# Own_USB-C_Breakout_v3_1_Final.net
KiCad netlist of a schematic drawn in EAGLE
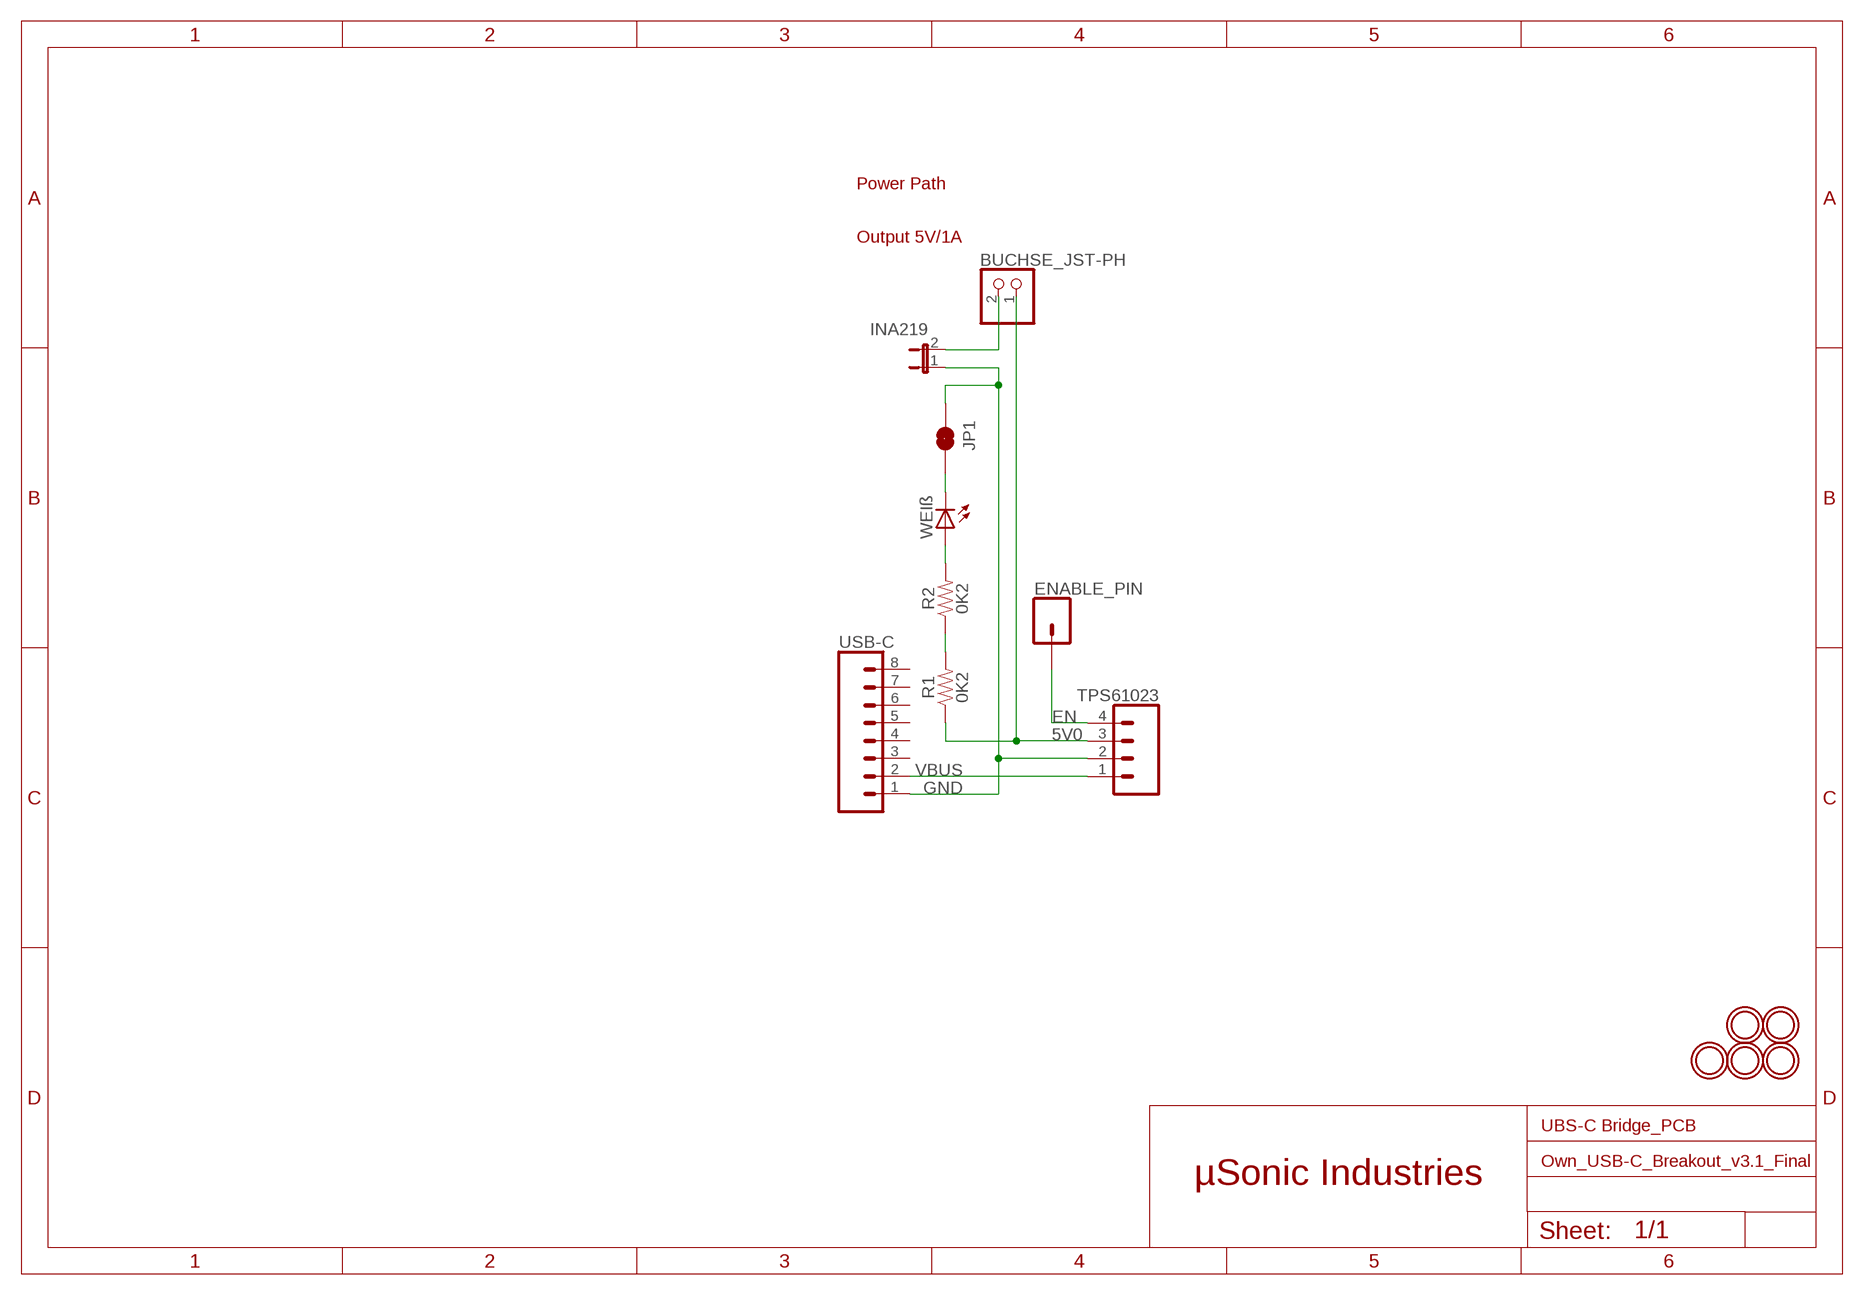
[diagram p0: schematic, sheet 1]

(export (version "E")
  (design (tool "Eeschema 10.0.6"))
  (components
    (comp (ref "BUCHSE_JST-PH")
      (value "JST_2PINOWN")
      (footprint "eagle-import:JST-PH-2-THMOWN")
      (libsource (lib "eagle-import") (part "JST_2PINOWN"))
    )
    (comp (ref "ENABLE_PIN")
      (value "CONN_01PTH_NO_SILK_YES_STOP")
      (footprint "eagle-import:1X01_NO_SILK")
      (libsource (lib "eagle-import") (part "CONN_01PTH_NO_SILK_YES_STOP"))
    )
    (comp (ref "INA219")
      (value "JP1E")
      (footprint "eagle-import:JP1")
      (libsource (lib "eagle-import") (part "JP1E"))
    )
    (comp (ref "JP1")
      (value "JUMPER-SMT_2_NC_TRACE_SILK")
      (footprint "eagle-import:SMT-JUMPER_2_NC_TRACE_SILK")
      (libsource (lib "eagle-import") (part "JUMPER-SMT_2_NC_TRACE_SILK"))
    )
    (comp (ref "R1")
      (value "0K2")
      (footprint "eagle-import:0805")
      (libsource (lib "eagle-import") (part "RESISTOR0805"))
    )
    (comp (ref "R2")
      (value "0K2")
      (footprint "eagle-import:0805")
      (libsource (lib "eagle-import") (part "RESISTOR0805"))
    )
    (comp (ref "TPS61023")
      (value "CONN_041X04_NO_SILK")
      (footprint "eagle-import:1X04_NO_SILK")
      (libsource (lib "eagle-import") (part "CONN_041X04_NO_SILK"))
    )
    (comp (ref "U$1")
      (value "MOUNTINGHOLE2.5")
      (footprint "eagle-import:MOUNTINGHOLE_2.5_PLATED")
      (libsource (lib "eagle-import") (part "MOUNTINGHOLE2.5"))
    )
    (comp (ref "U$2")
      (value "MOUNTINGHOLE2.5")
      (footprint "eagle-import:MOUNTINGHOLE_2.5_PLATED")
      (libsource (lib "eagle-import") (part "MOUNTINGHOLE2.5"))
    )
    (comp (ref "U$10")
      (value "MOUNTINGHOLE2.5")
      (footprint "eagle-import:MOUNTINGHOLE_2.5_PLATED")
      (libsource (lib "eagle-import") (part "MOUNTINGHOLE2.5"))
    )
    (comp (ref "U$11")
      (value "MOUNTINGHOLE2.5")
      (footprint "eagle-import:MOUNTINGHOLE_2.5_PLATED")
      (libsource (lib "eagle-import") (part "MOUNTINGHOLE2.5"))
    )
    (comp (ref "U$14")
      (value "MOUNTINGHOLE2.5")
      (footprint "eagle-import:MOUNTINGHOLE_2.5_PLATED")
      (libsource (lib "eagle-import") (part "MOUNTINGHOLE2.5"))
    )
    (comp (ref "USB-C")
      (value "CONN_08NO_SILK_FEMALE_PTH")
      (footprint "eagle-import:1X08_NO_SILK")
      (libsource (lib "eagle-import") (part "CONN_08NO_SILK_FEMALE_PTH"))
    )
    (comp (ref "WEIß")
      (value "LEDCHIPLED_0805")
      (footprint "eagle-import:CHIPLED_0805")
      (libsource (lib "eagle-import") (part "LEDCHIPLED_0805"))
    )
  )
  (nets
    (net (code "1") (name "/5V0") (class "Default")
      (node (ref "BUCHSE_JST-PH") (pin "1") (pinfunction "2_1") (pintype "passive"))
      (node (ref "R1") (pin "1") (pinfunction "1_1") (pintype "passive"))
      (node (ref "TPS61023") (pin "3") (pinfunction "3_3") (pintype "passive"))
    )
    (net (code "2") (name "/EN") (class "Default")
      (node (ref "ENABLE_PIN") (pin "1") (pinfunction "1_1") (pintype "passive"))
      (node (ref "TPS61023") (pin "4") (pinfunction "4_4") (pintype "passive"))
    )
    (net (code "3") (name "/GND") (class "Default")
      (node (ref "INA219") (pin "1") (pinfunction "1_1") (pintype "passive"))
      (node (ref "JP1") (pin "1") (pinfunction "1_1") (pintype "passive"))
      (node (ref "TPS61023") (pin "2") (pinfunction "2_2") (pintype "passive"))
      (node (ref "USB-C") (pin "1") (pinfunction "1_1") (pintype "passive"))
    )
    (net (code "4") (name "/VBUS") (class "Default")
      (node (ref "TPS61023") (pin "1") (pinfunction "1_1") (pintype "passive"))
      (node (ref "USB-C") (pin "2") (pinfunction "2_2") (pintype "passive"))
    )
    (net (code "5") (name "Net-(BUCHSE_JST-PH-1)") (class "Default")
      (node (ref "BUCHSE_JST-PH") (pin "2") (pinfunction "1_2") (pintype "passive"))
      (node (ref "INA219") (pin "2") (pinfunction "2_2") (pintype "passive"))
    )
    (net (code "6") (name "Net-(JP1-Pad2)") (class "Default")
      (node (ref "JP1") (pin "2") (pinfunction "2_2") (pintype "passive"))
      (node (ref "WEIß") (pin "C") (pinfunction "C_C") (pintype "passive"))
    )
    (net (code "7") (name "Net-(R1-Pad2)") (class "Default")
      (node (ref "R1") (pin "2") (pinfunction "2_2") (pintype "passive"))
      (node (ref "R2") (pin "1") (pinfunction "1_1") (pintype "passive"))
    )
    (net (code "8") (name "Net-(R2-Pad2)") (class "Default")
      (node (ref "R2") (pin "2") (pinfunction "2_2") (pintype "passive"))
      (node (ref "WEIß") (pin "A") (pinfunction "A_A") (pintype "passive"))
    )
    (net (code "9") (name "unconnected-(USB-C-Pad3)") (class "Default")
      (node (ref "USB-C") (pin "3") (pinfunction "3_3") (pintype "passive"))
    )
    (net (code "10") (name "unconnected-(USB-C-Pad4)") (class "Default")
      (node (ref "USB-C") (pin "4") (pinfunction "4_4") (pintype "passive"))
    )
    (net (code "11") (name "unconnected-(USB-C-Pad5)") (class "Default")
      (node (ref "USB-C") (pin "5") (pinfunction "5_5") (pintype "passive"))
    )
    (net (code "12") (name "unconnected-(USB-C-Pad6)") (class "Default")
      (node (ref "USB-C") (pin "6") (pinfunction "6_6") (pintype "passive"))
    )
    (net (code "13") (name "unconnected-(USB-C-Pad7)") (class "Default")
      (node (ref "USB-C") (pin "7") (pinfunction "7_7") (pintype "passive"))
    )
    (net (code "14") (name "unconnected-(USB-C-Pad8)") (class "Default")
      (node (ref "USB-C") (pin "8") (pinfunction "8_8") (pintype "passive"))
    )
  )
)
